# 795484912NUCLEO-DG_V3.net
KiCad netlist of a schematic drawn in Altium Designer
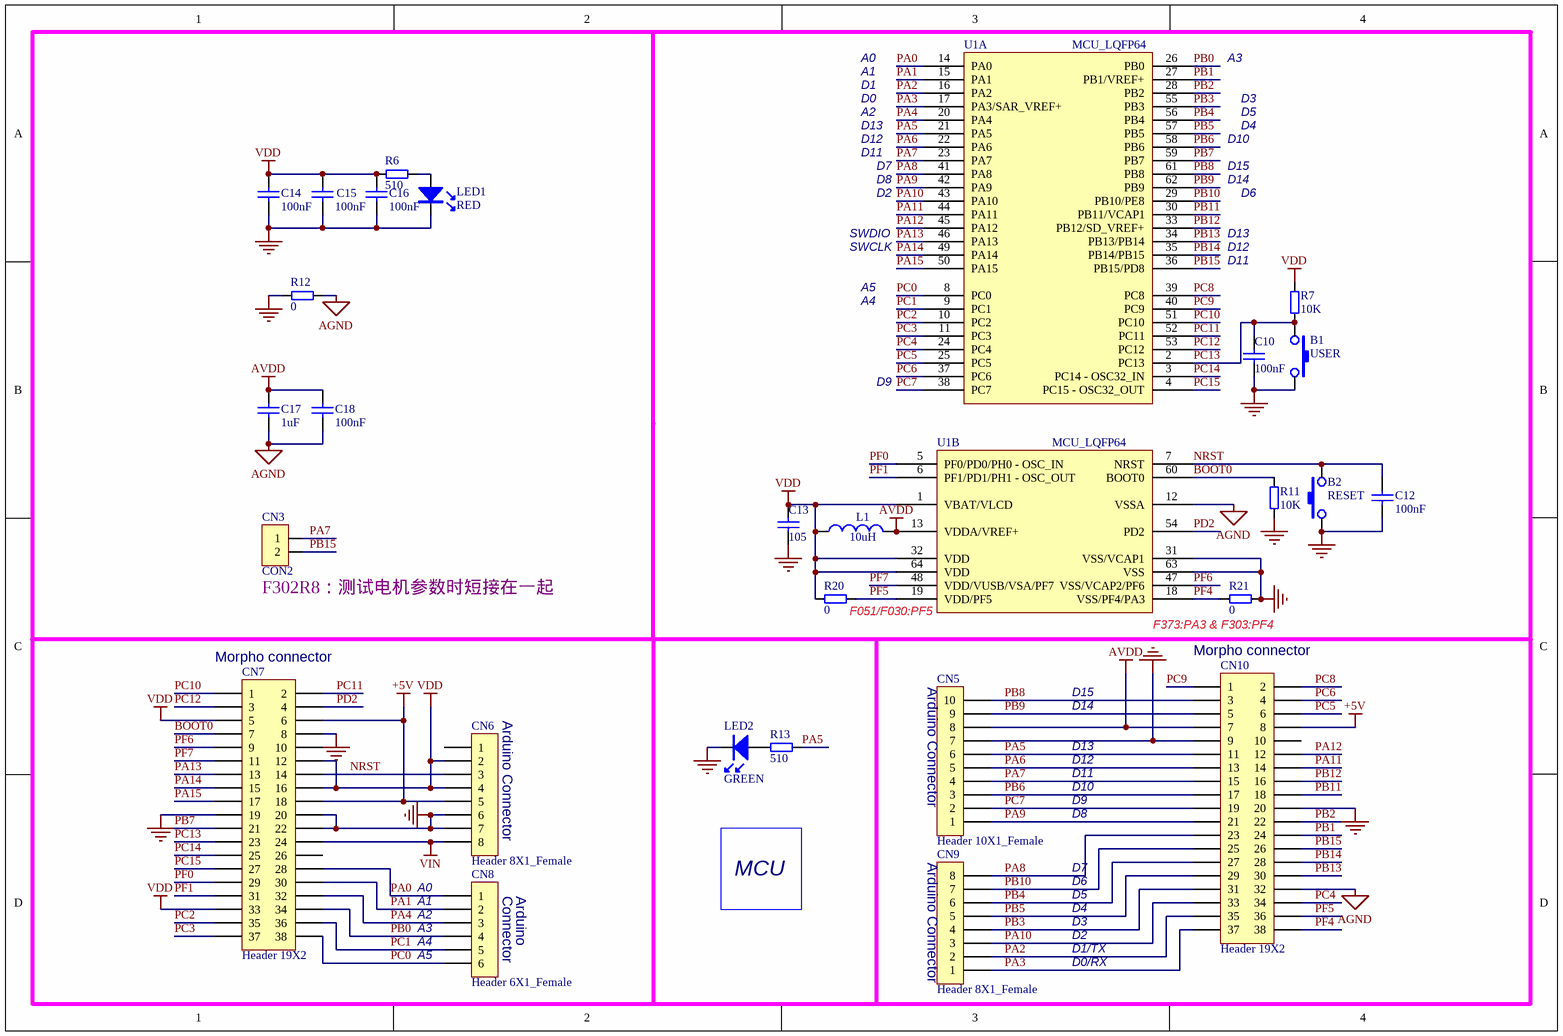
[diagram p0: 795484912NUCLEO-DG_V3.SchDoc]

(export (version "E")
  (design (tool "Eeschema 10.0.6"))
  (components
    (comp (ref "B1")
      (value "USER")
      (footprint "KG6*6TP")
      (description "K")
      (libsource (lib "zh") (part "SW6"))
    )
    (comp (ref "B2")
      (value "RESET")
      (footprint "KG6*6TP")
      (description "K")
      (libsource (lib "zh") (part "SW6"))
    )
    (comp (ref "C10")
      (value "100nF")
      (footprint "0603C")
      (description "Capacitor")
      (fields (field (name "PUBLISHER") "Altium Limited"))
      (libsource (lib "Miscellaneous Devices") (part "CAP"))
    )
    (comp (ref "C12")
      (value "100nF")
      (footprint "0603C")
      (description "Capacitor")
      (fields (field (name "PUBLISHER") "Altium Limited"))
      (libsource (lib "Miscellaneous Devices") (part "CAP"))
    )
    (comp (ref "C13")
      (value "105")
      (footprint "0603C")
      (description "0603  X5R 1礔")
      (fields (field (name "TOLERANCE") "10%"))
      (libsource (lib "MB963_1") (part "CAP SMD 0603  X5R 1礔 25V 10%"))
    )
    (comp (ref "C14")
      (value "100nF")
      (footprint "0603C")
      (description "Capacitor")
      (fields (field (name "PUBLISHER") "Altium Limited"))
      (libsource (lib "Miscellaneous Devices") (part "Cap"))
    )
    (comp (ref "C15")
      (value "100nF")
      (footprint "0603C")
      (description "Capacitor")
      (fields (field (name "PUBLISHER") "Altium Limited"))
      (libsource (lib "Miscellaneous Devices") (part "Cap"))
    )
    (comp (ref "C16")
      (value "100nF")
      (footprint "0603C")
      (description "Capacitor")
      (fields (field (name "PUBLISHER") "Altium Limited"))
      (libsource (lib "Miscellaneous Devices") (part "Cap"))
    )
    (comp (ref "C17")
      (value "1uF")
      (footprint "0603C")
      (description "Capacitor")
      (fields (field (name "PUBLISHER") "Altium Limited"))
      (libsource (lib "Miscellaneous Devices") (part "Cap"))
    )
    (comp (ref "C18")
      (value "100nF")
      (footprint "0603C")
      (description "Capacitor")
      (fields (field (name "PUBLISHER") "Altium Limited"))
      (libsource (lib "Miscellaneous Devices") (part "Cap"))
    )
    (comp (ref "CN3")
      (value "CON2")
      (footprint "SIP2")
      (description "J")
      (libsource (lib "zh") (part "CON2"))
    )
    (comp (ref "CN5")
      (value "Header 10X1_Female")
      (footprint "1*10P_FEMALE")
      (description "Header, 10-Pin, Single row,female")
      (fields (field (name "PUBLISHER") "Altium Limited"))
      (libsource (lib "Nucleo_64") (part "Header 10X1_Female"))
    )
    (comp (ref "CN6")
      (value "Header 8X1_Female")
      (footprint "1*8P_FEMALE")
      (description "Header, 8-Pin, Single row,female")
      (fields (field (name "PUBLISHER") "Altium Limited"))
      (libsource (lib "Nucleo_64") (part "Header 8X1_Female"))
    )
    (comp (ref "CN7")
      (value "Header 19X2")
      (footprint "2*19P")
      (description "Header, 19-Pin, Dual row")
      (fields (field (name "PUBLISHER") "Altium Limited"))
      (libsource (lib "Nucleo_64_1") (part "Header 19X2"))
    )
    (comp (ref "CN8")
      (value "Header 6X1_Female")
      (footprint "1*6P_FEMALE")
      (description "Header, 6-Pin, Single row,female")
      (fields (field (name "PUBLISHER") "Altium Limited"))
      (libsource (lib "Nucleo_64") (part "Header 6X1_Female"))
    )
    (comp (ref "CN9")
      (value "Header 8X1_Female")
      (footprint "1*8P_FEMALE")
      (description "Header, 8-Pin, Single row,female")
      (fields (field (name "PUBLISHER") "Altium Limited"))
      (libsource (lib "") (part "Header 8X1_Female_1"))
    )
    (comp (ref "CN10")
      (value "Header 19X2")
      (footprint "2*19P")
      (description "Header, 19-Pin, Dual row")
      (fields (field (name "PUBLISHER") "Altium Limited"))
      (libsource (lib "Nucleo_64_1") (part "Header 19X2"))
    )
    (comp (ref "L1")
      (value "10uH")
      (footprint "0603")
      (description "Inductor")
      (fields (field (name "PUBLISHER") "Altium Limited"))
      (libsource (lib "Miscellaneous Devices") (part "Inductor"))
    )
    (comp (ref "LED1")
      (value "RED")
      (footprint "0603D")
      (description "LED")
      (libsource (lib "zh") (part "LED"))
    )
    (comp (ref "LED2")
      (value "GREEN")
      (footprint "0603D")
      (description "LED")
      (libsource (lib "zh") (part "LED"))
    )
    (comp (ref "R6") (value "510") (footprint "0603") (description "10K") (libsource (lib "zh") (part "R")))
    (comp (ref "R7") (value "10K") (footprint "0603") (libsource (lib "zh") (part "R")))
    (comp (ref "R11") (value "10K") (footprint "0603") (libsource (lib "zh") (part "R")))
    (comp (ref "R12") (value "0") (footprint "0603") (description "10K") (libsource (lib "zh") (part "R")))
    (comp (ref "R13") (value "510") (footprint "0603") (description "10K") (libsource (lib "zh") (part "R")))
    (comp (ref "R20") (value "0") (footprint "0603") (description "10K") (libsource (lib "zh") (part "R")))
    (comp (ref "R21") (value "0") (footprint "0603") (description "10K") (libsource (lib "zh") (part "R")))
    (comp (ref "U1")
      (value "MCU_LQFP64")
      (footprint "LQFP-64")
      (libsource (lib "Nucleo_64") (part "MCU_LQFP64"))
    )
  )
  (nets
    (net (code "1") (name "+5V") (class "Default")
      (node (ref "CN10") (pin "8") (pinfunction "8_8") (pintype "passive"))
      (node (ref "CN6") (pin "5") (pinfunction "5_5") (pintype "passive"))
      (node (ref "CN7") (pin "18") (pinfunction "18_18") (pintype "passive"))
      (node (ref "CN7") (pin "6") (pinfunction "6_6") (pintype "passive"))
    )
    (net (code "2") (name "/BOOT0") (class "Default")
      (node (ref "CN7") (pin "7") (pinfunction "7_7") (pintype "passive"))
      (node (ref "R11") (pin "2") (pinfunction "2_2") (pintype "passive"))
      (node (ref "U1") (pin "60") (pinfunction "BOOT0_60") (pintype "passive"))
    )
    (net (code "3") (name "/NRST") (class "Default")
      (node (ref "B2") (pin "2") (pintype "passive"))
      (node (ref "C12") (pin "2") (pinfunction "2_2") (pintype "passive"))
      (node (ref "CN6") (pin "3") (pinfunction "3_3") (pintype "passive"))
      (node (ref "CN7") (pin "14") (pinfunction "14_14") (pintype "passive"))
      (node (ref "U1") (pin "7") (pinfunction "NRST_7") (pintype "passive"))
    )
    (net (code "4") (name "/PA0") (class "Default")
      (node (ref "CN7") (pin "28") (pinfunction "28_28") (pintype "passive"))
      (node (ref "CN8") (pin "1") (pinfunction "1_1") (pintype "passive"))
      (node (ref "U1") (pin "14") (pinfunction "PA0_14") (pintype "passive"))
    )
    (net (code "5") (name "/PA1") (class "Default")
      (node (ref "CN7") (pin "30") (pinfunction "30_30") (pintype "passive"))
      (node (ref "CN8") (pin "2") (pinfunction "2_2") (pintype "passive"))
      (node (ref "U1") (pin "15") (pinfunction "PA1_15") (pintype "passive"))
    )
    (net (code "6") (name "/PA2") (class "Default")
      (node (ref "CN10") (pin "35") (pinfunction "35_35") (pintype "passive"))
      (node (ref "CN9") (pin "2") (pinfunction "2_2") (pintype "passive"))
      (node (ref "U1") (pin "16") (pinfunction "PA2_16") (pintype "passive"))
    )
    (net (code "7") (name "/PA3") (class "Default")
      (node (ref "CN10") (pin "37") (pinfunction "37_37") (pintype "passive"))
      (node (ref "CN9") (pin "1") (pinfunction "1_1") (pintype "passive"))
      (node (ref "U1") (pin "17") (pinfunction "PA3/SAR_VREF+_17") (pintype "passive"))
    )
    (net (code "8") (name "/PA4") (class "Default")
      (node (ref "CN7") (pin "32") (pinfunction "32_32") (pintype "passive"))
      (node (ref "CN8") (pin "3") (pinfunction "3_3") (pintype "passive"))
      (node (ref "U1") (pin "20") (pinfunction "PA4_20") (pintype "passive"))
    )
    (net (code "9") (name "/PA5") (class "Default")
      (node (ref "CN10") (pin "11") (pinfunction "11_11") (pintype "passive"))
      (node (ref "CN5") (pin "6") (pinfunction "6_6") (pintype "passive"))
      (node (ref "R13") (pin "2") (pinfunction "2_2") (pintype "passive"))
      (node (ref "U1") (pin "21") (pinfunction "PA5_21") (pintype "passive"))
    )
    (net (code "10") (name "/PA6") (class "Default")
      (node (ref "CN10") (pin "13") (pinfunction "13_13") (pintype "passive"))
      (node (ref "CN5") (pin "5") (pinfunction "5_5") (pintype "passive"))
      (node (ref "U1") (pin "22") (pinfunction "PA6_22") (pintype "passive"))
    )
    (net (code "11") (name "/PA7") (class "Default")
      (node (ref "CN10") (pin "15") (pinfunction "15_15") (pintype "passive"))
      (node (ref "CN3") (pin "1") (pinfunction "1_1") (pintype "passive"))
      (node (ref "CN5") (pin "4") (pinfunction "4_4") (pintype "passive"))
      (node (ref "U1") (pin "23") (pinfunction "PA7_23") (pintype "passive"))
    )
    (net (code "12") (name "/PA8") (class "Default")
      (node (ref "CN10") (pin "23") (pinfunction "23_23") (pintype "passive"))
      (node (ref "CN9") (pin "8") (pinfunction "8_8") (pintype "passive"))
      (node (ref "U1") (pin "41") (pinfunction "PA8_41") (pintype "passive"))
    )
    (net (code "13") (name "/PA9") (class "Default")
      (node (ref "CN10") (pin "21") (pinfunction "21_21") (pintype "passive"))
      (node (ref "CN5") (pin "1") (pinfunction "1_1") (pintype "passive"))
      (node (ref "U1") (pin "42") (pinfunction "PA9_42") (pintype "passive"))
    )
    (net (code "14") (name "/PA10") (class "Default")
      (node (ref "CN10") (pin "33") (pinfunction "33_33") (pintype "passive"))
      (node (ref "CN9") (pin "3") (pinfunction "3_3") (pintype "passive"))
      (node (ref "U1") (pin "43") (pinfunction "PA10_43") (pintype "passive"))
    )
    (net (code "15") (name "/PA11") (class "Default")
      (node (ref "CN10") (pin "14") (pinfunction "14_14") (pintype "passive"))
      (node (ref "U1") (pin "44") (pinfunction "PA11_44") (pintype "passive"))
    )
    (net (code "16") (name "/PA12") (class "Default")
      (node (ref "CN10") (pin "12") (pinfunction "12_12") (pintype "passive"))
      (node (ref "U1") (pin "45") (pinfunction "PA12_45") (pintype "passive"))
    )
    (net (code "17") (name "/PA13") (class "Default")
      (node (ref "CN7") (pin "13") (pinfunction "13_13") (pintype "passive"))
      (node (ref "U1") (pin "46") (pinfunction "PA13_46") (pintype "passive"))
    )
    (net (code "18") (name "/PA14") (class "Default")
      (node (ref "CN7") (pin "15") (pinfunction "15_15") (pintype "passive"))
      (node (ref "U1") (pin "49") (pinfunction "PA14_49") (pintype "passive"))
    )
    (net (code "19") (name "/PA15") (class "Default")
      (node (ref "CN7") (pin "17") (pinfunction "17_17") (pintype "passive"))
      (node (ref "U1") (pin "50") (pinfunction "PA15_50") (pintype "passive"))
    )
    (net (code "20") (name "/PB0") (class "Default")
      (node (ref "CN7") (pin "34") (pinfunction "34_34") (pintype "passive"))
      (node (ref "CN8") (pin "4") (pinfunction "4_4") (pintype "passive"))
      (node (ref "U1") (pin "26") (pinfunction "PB0_26") (pintype "passive"))
    )
    (net (code "21") (name "/PB1") (class "Default")
      (node (ref "CN10") (pin "24") (pinfunction "24_24") (pintype "passive"))
      (node (ref "U1") (pin "27") (pinfunction "PB1/VREF+_27") (pintype "passive"))
    )
    (net (code "22") (name "/PB2") (class "Default")
      (node (ref "CN10") (pin "22") (pinfunction "22_22") (pintype "passive"))
      (node (ref "U1") (pin "28") (pinfunction "PB2_28") (pintype "passive"))
    )
    (net (code "23") (name "/PB3") (class "Default")
      (node (ref "CN10") (pin "31") (pinfunction "31_31") (pintype "passive"))
      (node (ref "CN9") (pin "4") (pinfunction "4_4") (pintype "passive"))
      (node (ref "U1") (pin "55") (pinfunction "PB3_55") (pintype "passive"))
    )
    (net (code "24") (name "/PB4") (class "Default")
      (node (ref "CN10") (pin "27") (pinfunction "27_27") (pintype "passive"))
      (node (ref "CN9") (pin "6") (pinfunction "6_6") (pintype "passive"))
      (node (ref "U1") (pin "56") (pinfunction "PB4_56") (pintype "passive"))
    )
    (net (code "25") (name "/PB5") (class "Default")
      (node (ref "CN10") (pin "29") (pinfunction "29_29") (pintype "passive"))
      (node (ref "CN9") (pin "5") (pinfunction "5_5") (pintype "passive"))
      (node (ref "U1") (pin "57") (pinfunction "PB5_57") (pintype "passive"))
    )
    (net (code "26") (name "/PB6") (class "Default")
      (node (ref "CN10") (pin "17") (pinfunction "17_17") (pintype "passive"))
      (node (ref "CN5") (pin "3") (pinfunction "3_3") (pintype "passive"))
      (node (ref "U1") (pin "58") (pinfunction "PB6_58") (pintype "passive"))
    )
    (net (code "27") (name "/PB7") (class "Default")
      (node (ref "CN7") (pin "21") (pinfunction "21_21") (pintype "passive"))
      (node (ref "U1") (pin "59") (pinfunction "PB7_59") (pintype "passive"))
    )
    (net (code "28") (name "/PB8") (class "Default")
      (node (ref "CN10") (pin "3") (pinfunction "3_3") (pintype "passive"))
      (node (ref "CN5") (pin "10") (pinfunction "10_10") (pintype "passive"))
      (node (ref "U1") (pin "61") (pinfunction "PB8_61") (pintype "passive"))
    )
    (net (code "29") (name "/PB9") (class "Default")
      (node (ref "CN10") (pin "5") (pinfunction "5_5") (pintype "passive"))
      (node (ref "CN5") (pin "9") (pinfunction "9_9") (pintype "passive"))
      (node (ref "U1") (pin "62") (pinfunction "PB9_62") (pintype "passive"))
    )
    (net (code "30") (name "/PB10") (class "Default")
      (node (ref "CN10") (pin "25") (pinfunction "25_25") (pintype "passive"))
      (node (ref "CN9") (pin "7") (pinfunction "7_7") (pintype "passive"))
      (node (ref "U1") (pin "29") (pinfunction "PB10/PE8_29") (pintype "passive"))
    )
    (net (code "31") (name "/PB11") (class "Default")
      (node (ref "CN10") (pin "18") (pinfunction "18_18") (pintype "passive"))
      (node (ref "U1") (pin "30") (pinfunction "PB11/VCAP1_30") (pintype "passive"))
    )
    (net (code "32") (name "/PB12") (class "Default")
      (node (ref "CN10") (pin "16") (pinfunction "16_16") (pintype "passive"))
      (node (ref "U1") (pin "33") (pinfunction "PB12/SD_VREF+_33") (pintype "passive"))
    )
    (net (code "33") (name "/PB13") (class "Default")
      (node (ref "CN10") (pin "30") (pinfunction "30_30") (pintype "passive"))
      (node (ref "U1") (pin "34") (pinfunction "PB13/PB14_34") (pintype "passive"))
    )
    (net (code "34") (name "/PB14") (class "Default")
      (node (ref "CN10") (pin "28") (pinfunction "28_28") (pintype "passive"))
      (node (ref "U1") (pin "35") (pinfunction "PB14/PB15_35") (pintype "passive"))
    )
    (net (code "35") (name "/PB15") (class "Default")
      (node (ref "CN10") (pin "26") (pinfunction "26_26") (pintype "passive"))
      (node (ref "CN3") (pin "2") (pinfunction "2_2") (pintype "passive"))
      (node (ref "U1") (pin "36") (pinfunction "PB15/PD8_36") (pintype "passive"))
    )
    (net (code "36") (name "/PC0") (class "Default")
      (node (ref "CN7") (pin "38") (pinfunction "38_38") (pintype "passive"))
      (node (ref "CN8") (pin "6") (pinfunction "6_6") (pintype "passive"))
      (node (ref "U1") (pin "8") (pinfunction "PC0_8") (pintype "passive"))
    )
    (net (code "37") (name "/PC1") (class "Default")
      (node (ref "CN7") (pin "36") (pinfunction "36_36") (pintype "passive"))
      (node (ref "CN8") (pin "5") (pinfunction "5_5") (pintype "passive"))
      (node (ref "U1") (pin "9") (pinfunction "PC1_9") (pintype "passive"))
    )
    (net (code "38") (name "/PC2") (class "Default")
      (node (ref "CN7") (pin "35") (pinfunction "35_35") (pintype "passive"))
      (node (ref "U1") (pin "10") (pinfunction "PC2_10") (pintype "passive"))
    )
    (net (code "39") (name "/PC3") (class "Default")
      (node (ref "CN7") (pin "37") (pinfunction "37_37") (pintype "passive"))
      (node (ref "U1") (pin "11") (pinfunction "PC3_11") (pintype "passive"))
    )
    (net (code "40") (name "/PC4") (class "Default")
      (node (ref "CN10") (pin "34") (pinfunction "34_34") (pintype "passive"))
      (node (ref "U1") (pin "24") (pinfunction "PC4_24") (pintype "passive"))
    )
    (net (code "41") (name "/PC5") (class "Default")
      (node (ref "CN10") (pin "6") (pinfunction "6_6") (pintype "passive"))
      (node (ref "U1") (pin "25") (pinfunction "PC5_25") (pintype "passive"))
    )
    (net (code "42") (name "/PC6") (class "Default")
      (node (ref "CN10") (pin "4") (pinfunction "4_4") (pintype "passive"))
      (node (ref "U1") (pin "37") (pinfunction "PC6_37") (pintype "passive"))
    )
    (net (code "43") (name "/PC7") (class "Default")
      (node (ref "CN10") (pin "19") (pinfunction "19_19") (pintype "passive"))
      (node (ref "CN5") (pin "2") (pinfunction "2_2") (pintype "passive"))
      (node (ref "U1") (pin "38") (pinfunction "PC7_38") (pintype "passive"))
    )
    (net (code "44") (name "/PC8") (class "Default")
      (node (ref "CN10") (pin "2") (pinfunction "2_2") (pintype "passive"))
      (node (ref "U1") (pin "39") (pinfunction "PC8_39") (pintype "passive"))
    )
    (net (code "45") (name "/PC9") (class "Default")
      (node (ref "CN10") (pin "1") (pinfunction "1_1") (pintype "passive"))
      (node (ref "U1") (pin "40") (pinfunction "PC9_40") (pintype "passive"))
    )
    (net (code "46") (name "/PC10") (class "Default")
      (node (ref "CN7") (pin "1") (pinfunction "1_1") (pintype "passive"))
      (node (ref "U1") (pin "51") (pinfunction "PC10_51") (pintype "passive"))
    )
    (net (code "47") (name "/PC11") (class "Default")
      (node (ref "CN7") (pin "2") (pinfunction "2_2") (pintype "passive"))
      (node (ref "U1") (pin "52") (pinfunction "PC11_52") (pintype "passive"))
    )
    (net (code "48") (name "/PC12") (class "Default")
      (node (ref "CN7") (pin "3") (pinfunction "3_3") (pintype "passive"))
      (node (ref "U1") (pin "53") (pinfunction "PC12_53") (pintype "passive"))
    )
    (net (code "49") (name "/PC13") (class "Default")
      (node (ref "B1") (pin "2") (pintype "passive"))
      (node (ref "C10") (pin "2") (pinfunction "2_2") (pintype "passive"))
      (node (ref "CN7") (pin "23") (pinfunction "23_23") (pintype "passive"))
      (node (ref "R7") (pin "1") (pinfunction "1_1") (pintype "passive"))
      (node (ref "U1") (pin "2") (pinfunction "PC13_2") (pintype "passive"))
    )
    (net (code "50") (name "/PC14") (class "Default")
      (node (ref "CN7") (pin "25") (pinfunction "25_25") (pintype "passive"))
      (node (ref "U1") (pin "3") (pinfunction "PC14_-_OSC32_IN_3") (pintype "passive"))
    )
    (net (code "51") (name "/PC15") (class "Default")
      (node (ref "CN7") (pin "27") (pinfunction "27_27") (pintype "passive"))
      (node (ref "U1") (pin "4") (pinfunction "PC15_-_OSC32_OUT_4") (pintype "passive"))
    )
    (net (code "52") (name "/PD2") (class "Default")
      (node (ref "CN7") (pin "4") (pinfunction "4_4") (pintype "passive"))
      (node (ref "U1") (pin "54") (pinfunction "PD2_54") (pintype "passive"))
    )
    (net (code "53") (name "/PF0") (class "Default")
      (node (ref "CN7") (pin "29") (pinfunction "29_29") (pintype "passive"))
      (node (ref "U1") (pin "5") (pinfunction "PF0/PD0/PH0_-_OSC_IN_5") (pintype "passive"))
    )
    (net (code "54") (name "/PF1") (class "Default")
      (node (ref "CN7") (pin "31") (pinfunction "31_31") (pintype "passive"))
      (node (ref "U1") (pin "6") (pinfunction "PF1/PD1/PH1_-_OSC_OUT_6") (pintype "passive"))
    )
    (net (code "55") (name "/PF4") (class "Default")
      (node (ref "CN10") (pin "38") (pinfunction "38_38") (pintype "passive"))
      (node (ref "R21") (pin "2") (pinfunction "2_2") (pintype "passive"))
      (node (ref "U1") (pin "18") (pinfunction "VSS/PF4/PA3_18") (pintype "passive"))
    )
    (net (code "56") (name "/PF5") (class "Default")
      (node (ref "CN10") (pin "36") (pinfunction "36_36") (pintype "passive"))
      (node (ref "R20") (pin "1") (pinfunction "1_1") (pintype "passive"))
      (node (ref "U1") (pin "19") (pinfunction "VDD/PF5_19") (pintype "passive"))
    )
    (net (code "57") (name "/PF6") (class "Default")
      (node (ref "CN7") (pin "9") (pinfunction "9_9") (pintype "passive"))
      (node (ref "U1") (pin "47") (pinfunction "VSS/VCAP2/PF6_47") (pintype "passive"))
    )
    (net (code "58") (name "/PF7") (class "Default")
      (node (ref "CN7") (pin "11") (pinfunction "11_11") (pintype "passive"))
      (node (ref "U1") (pin "48") (pinfunction "VDD/VUSB/VSA/PF7_48") (pintype "passive"))
    )
    (net (code "59") (name "AGND") (class "Default")
      (node (ref "C17") (pin "2") (pinfunction "2_2") (pintype "passive"))
      (node (ref "C18") (pin "2") (pinfunction "2_2") (pintype "passive"))
      (node (ref "CN10") (pin "32") (pinfunction "32_32") (pintype "passive"))
      (node (ref "R12") (pin "2") (pinfunction "2_2") (pintype "passive"))
      (node (ref "U1") (pin "12") (pinfunction "VSSA_12") (pintype "passive"))
    )
    (net (code "60") (name "AVDD") (class "Default")
      (node (ref "C17") (pin "1") (pinfunction "1_1") (pintype "passive"))
      (node (ref "C18") (pin "1") (pinfunction "1_1") (pintype "passive"))
      (node (ref "CN10") (pin "7") (pinfunction "7_7") (pintype "passive"))
      (node (ref "CN5") (pin "8") (pinfunction "8_8") (pintype "passive"))
      (node (ref "L1") (pin "2") (pinfunction "2_2") (pintype "passive"))
      (node (ref "U1") (pin "13") (pinfunction "VDDA/VREF+_13") (pintype "passive"))
    )
    (net (code "61") (name "GND") (class "Default")
      (node (ref "B1") (pin "1") (pintype "passive"))
      (node (ref "B2") (pin "1") (pintype "passive"))
      (node (ref "C10") (pin "1") (pinfunction "1_1") (pintype "passive"))
      (node (ref "C12") (pin "1") (pinfunction "1_1") (pintype "passive"))
      (node (ref "C13") (pin "2") (pinfunction "2_2") (pintype "passive"))
      (node (ref "C14") (pin "2") (pinfunction "2_2") (pintype "passive"))
      (node (ref "C15") (pin "2") (pinfunction "2_2") (pintype "passive"))
      (node (ref "C16") (pin "2") (pinfunction "2_2") (pintype "passive"))
      (node (ref "CN10") (pin "20") (pinfunction "20_20") (pintype "passive"))
      (node (ref "CN10") (pin "9") (pinfunction "9_9") (pintype "passive"))
      (node (ref "CN5") (pin "7") (pinfunction "7_7") (pintype "passive"))
      (node (ref "CN6") (pin "6") (pinfunction "6_6") (pintype "passive"))
      (node (ref "CN6") (pin "7") (pinfunction "7_7") (pintype "passive"))
      (node (ref "CN7") (pin "19") (pinfunction "19_19") (pintype "passive"))
      (node (ref "CN7") (pin "20") (pinfunction "20_20") (pintype "passive"))
      (node (ref "CN7") (pin "22") (pinfunction "22_22") (pintype "passive"))
      (node (ref "CN7") (pin "8") (pinfunction "8_8") (pintype "passive"))
      (node (ref "LED1") (pin "K") (pinfunction "K_K") (pintype "passive"))
      (node (ref "LED2") (pin "K") (pinfunction "K_K") (pintype "passive"))
      (node (ref "R11") (pin "1") (pinfunction "1_1") (pintype "passive"))
      (node (ref "R12") (pin "1") (pinfunction "1_1") (pintype "passive"))
      (node (ref "R21") (pin "1") (pinfunction "1_1") (pintype "passive"))
      (node (ref "U1") (pin "31") (pinfunction "VSS/VCAP1_31") (pintype "passive"))
      (node (ref "U1") (pin "63") (pinfunction "VSS_63") (pintype "passive"))
    )
    (net (code "62") (name "Net-(LED1-PadA)") (class "Default")
      (node (ref "LED1") (pin "A") (pinfunction "A_A") (pintype "passive"))
      (node (ref "R6") (pin "1") (pinfunction "1_1") (pintype "passive"))
    )
    (net (code "63") (name "Net-(LED2-PadA)") (class "Default")
      (node (ref "LED2") (pin "A") (pinfunction "A_A") (pintype "passive"))
      (node (ref "R13") (pin "1") (pinfunction "1_1") (pintype "passive"))
    )
    (net (code "64") (name "VDD") (class "Default")
      (node (ref "C13") (pin "1") (pinfunction "1_1") (pintype "passive"))
      (node (ref "C14") (pin "1") (pinfunction "1_1") (pintype "passive"))
      (node (ref "C15") (pin "1") (pinfunction "1_1") (pintype "passive"))
      (node (ref "C16") (pin "1") (pinfunction "1_1") (pintype "passive"))
      (node (ref "CN6") (pin "2") (pinfunction "2_2") (pintype "passive"))
      (node (ref "CN6") (pin "4") (pinfunction "4_4") (pintype "passive"))
      (node (ref "CN7") (pin "12") (pinfunction "12_12") (pintype "passive"))
      (node (ref "CN7") (pin "16") (pinfunction "16_16") (pintype "passive"))
      (node (ref "CN7") (pin "33") (pinfunction "33_33") (pintype "passive"))
      (node (ref "CN7") (pin "5") (pinfunction "5_5") (pintype "passive"))
      (node (ref "L1") (pin "1") (pinfunction "1_1") (pintype "passive"))
      (node (ref "R20") (pin "2") (pinfunction "2_2") (pintype "passive"))
      (node (ref "R6") (pin "2") (pinfunction "2_2") (pintype "passive"))
      (node (ref "R7") (pin "2") (pinfunction "2_2") (pintype "passive"))
      (node (ref "U1") (pin "1") (pinfunction "VBAT/VLCD_1") (pintype "passive"))
      (node (ref "U1") (pin "32") (pinfunction "VDD_32") (pintype "passive"))
      (node (ref "U1") (pin "64") (pinfunction "VDD_64") (pintype "passive"))
    )
    (net (code "65") (name "VIN") (class "Default")
      (node (ref "CN6") (pin "8") (pinfunction "8_8") (pintype "passive"))
      (node (ref "CN7") (pin "24") (pinfunction "24_24") (pintype "passive"))
    )
    (net (code "66") (name "unconnected-(CN6-Pad1)") (class "Default")
      (node (ref "CN6") (pin "1") (pinfunction "1_1") (pintype "passive"))
    )
    (net (code "67") (name "unconnected-(CN7-Pad10)") (class "Default")
      (node (ref "CN7") (pin "10") (pinfunction "10_10") (pintype "passive"))
    )
    (net (code "68") (name "unconnected-(CN7-Pad26)") (class "Default")
      (node (ref "CN7") (pin "26") (pinfunction "26_26") (pintype "passive"))
    )
    (net (code "69") (name "unconnected-(CN10-Pad10)") (class "Default")
      (node (ref "CN10") (pin "10") (pinfunction "10_10") (pintype "passive"))
    )
  )
)
